# Frost5000_Sch.net
KiCad netlist of a schematic drawn in Altium Designer
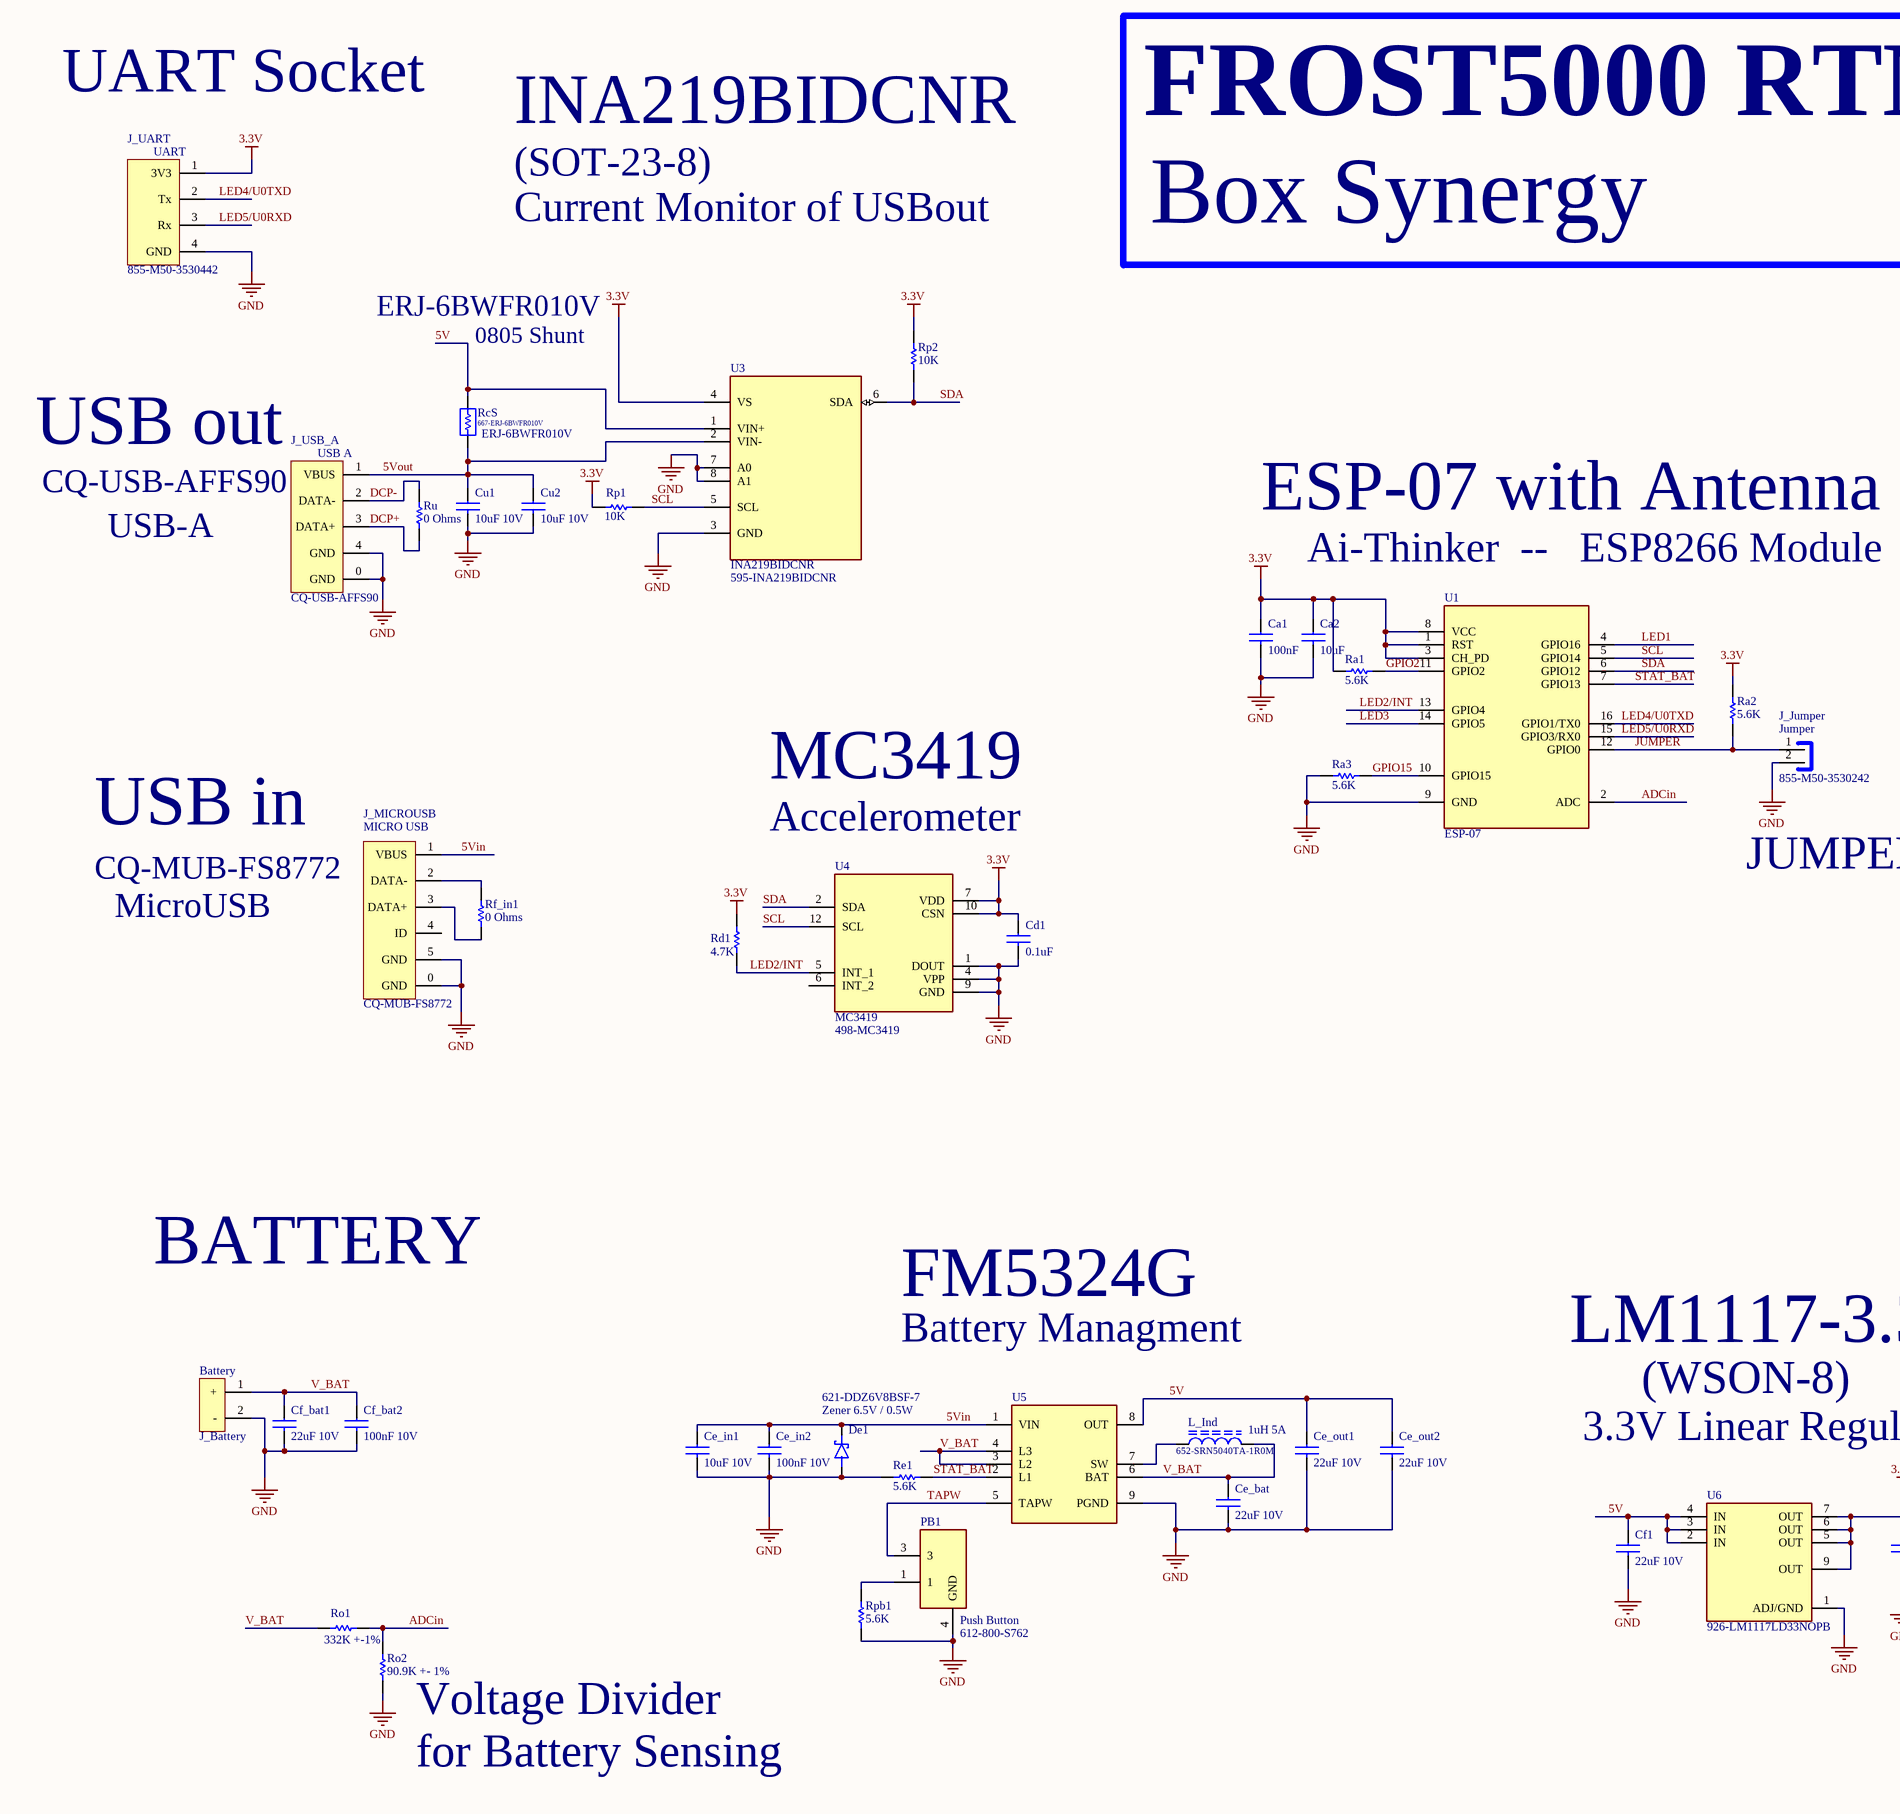
[diagram p0: Frost5000_Sch.SchDoc, left]
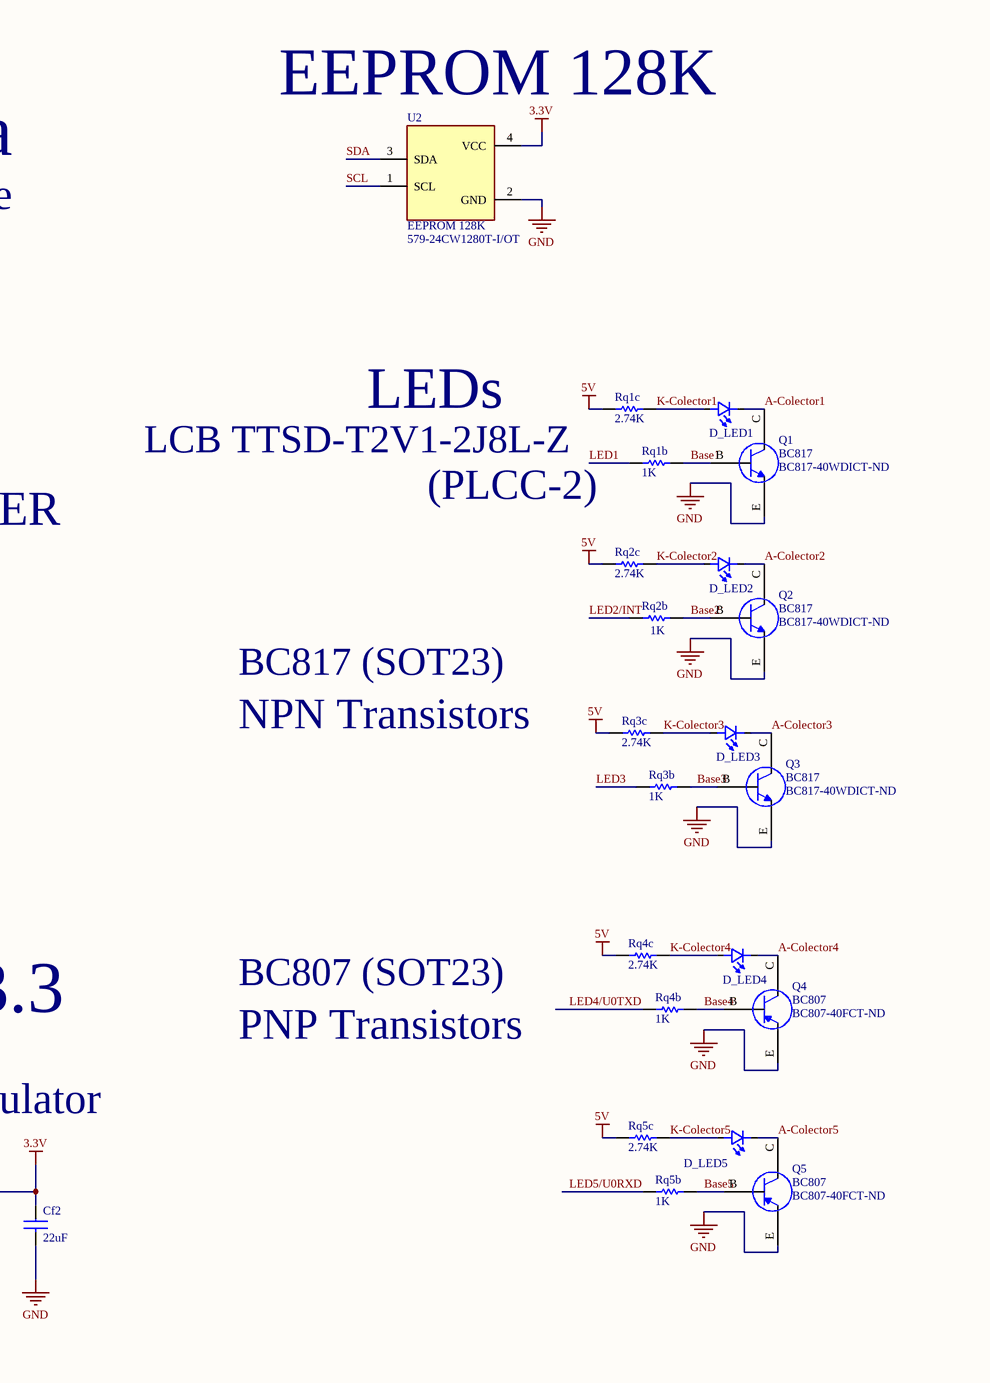
[diagram p1: Frost5000_Sch.SchDoc, right]

(export (version "E")
  (design (tool "Eeschema 10.0.6"))
  (components
    (comp (ref "Ca1")
      (value "100nF")
      (footprint "CAP_0603")
      (description "Capac Ceramic SMD 0603")
      (libsource (lib "Frost5000Beta_LIB_Pasivos_Sch") (part "Cap_0603_Ceramic"))
    )
    (comp (ref "Ca2")
      (value "10uF")
      (footprint "CAP_1206")
      (description "Capac Ceramic SMD")
      (libsource (lib "Frost5000Beta_LIB_Pasivos_Sch") (part "Cap_1206_Ceramic"))
    )
    (comp (ref "Cd1")
      (value "0.1uF")
      (footprint "CAP_0603")
      (description "Capac Ceramic SMD 0603")
      (libsource (lib "Frost5000Beta_LIB_Pasivos_Sch") (part "Cap_0603_Ceramic"))
    )
    (comp (ref "Ce_bat")
      (value "22uF 10V")
      (footprint "CAP_1206")
      (description "Capac Ceramic SMD")
      (libsource (lib "Frost5000Beta_LIB_Pasivos_Sch") (part "Cap_1206_Ceramic"))
    )
    (comp (ref "Ce_in1")
      (value "10uF 10V")
      (footprint "CAP_1206")
      (description "Capac Ceramic SMD")
      (libsource (lib "Frost5000Beta_LIB_Pasivos_Sch") (part "Cap_1206_Ceramic"))
    )
    (comp (ref "Ce_in2")
      (value "100nF 10V")
      (footprint "CAP_0603")
      (description "Capac Ceramic SMD 0603")
      (libsource (lib "Frost5000Beta_LIB_Pasivos_Sch") (part "Cap_0603_Ceramic"))
    )
    (comp (ref "Ce_out1")
      (value "22uF 10V")
      (footprint "CAP_1210")
      (description "Capac Ceramic SMD 1210")
      (libsource (lib "Frost5000Beta_LIB_Pasivos_Sch") (part "Cap_1210_Ceramic"))
    )
    (comp (ref "Ce_out2")
      (value "22uF 10V")
      (footprint "CAP_1206")
      (description "Capac Ceramic SMD")
      (libsource (lib "Frost5000Beta_LIB_Pasivos_Sch") (part "Cap_1206_Ceramic"))
    )
    (comp (ref "Cf1")
      (value "22uF 10V")
      (footprint "CAP_0603")
      (description "Capac Ceramic SMD 0603")
      (libsource (lib "Frost5000Beta_LIB_Pasivos_Sch") (part "Cap_0603_Ceramic"))
    )
    (comp (ref "Cf2")
      (value "22uF")
      (footprint "CAP_0603")
      (description "Capac Ceramic SMD 0603")
      (libsource (lib "Frost5000Beta_LIB_Pasivos_Sch") (part "Cap_0603_Ceramic"))
    )
    (comp (ref "Cf_bat1")
      (value "22uF 10V")
      (footprint "CAP_1206")
      (description "Capac Ceramic SMD")
      (libsource (lib "Frost5000Beta_LIB_Pasivos_Sch") (part "Cap_1206_Ceramic"))
    )
    (comp (ref "Cf_bat2")
      (value "100nF 10V")
      (footprint "CAP_0603")
      (description "Capac Ceramic SMD 0603")
      (libsource (lib "Frost5000Beta_LIB_Pasivos_Sch") (part "Cap_0603_Ceramic"))
    )
    (comp (ref "Cu1")
      (value "10uF 10V")
      (footprint "CAP_1206")
      (description "Capac Ceramic SMD")
      (libsource (lib "Frost5000Beta_LIB_Pasivos_Sch") (part "Cap_1206_Ceramic"))
    )
    (comp (ref "Cu2")
      (value "10uF 10V")
      (footprint "CAP_1206")
      (description "Capac Ceramic SMD")
      (libsource (lib "Frost5000Beta_LIB_Pasivos_Sch") (part "Cap_1206_Ceramic"))
    )
    (comp (ref "De1")
      (value "Zener 6.5V / 0.5W")
      (footprint "Zener-SOD323F")
      (fields
        (field (name "MF") "Littelfuse")
        (field (name "MP") "SMF5.0AT1G")
        (field (name "SUPPLIER PART NUMBER 1") "621-DDZ6V8BSF-7")
      )
      (libsource (lib "Frost5000Beta_LIB_Otros_Sch") (part "Zener"))
    )
    (comp (ref "D_LED1")
      (value "LCB TTSD-T2V1-2J8L-Z")
      (footprint "LED_PLCC-2")
      (description "Blue LED PLCC-2")
      (fields (field (name "MF") "Broadcom Limited") (field (name "MP") "HSMW-C191"))
      (libsource (lib "Frost5000Beta_LIB_Otros_Sch") (part "LCB_TTSD"))
    )
    (comp (ref "D_LED2")
      (value "LCB TTSD-T2V1-2J8L-Z")
      (footprint "LED_PLCC-2")
      (description "Blue LED PLCC-2")
      (fields (field (name "MF") "Broadcom Limited") (field (name "MP") "HSMW-C191"))
      (libsource (lib "Frost5000Beta_LIB_Otros_Sch") (part "LCB_TTSD"))
    )
    (comp (ref "D_LED3")
      (value "LCB TTSD-T2V1-2J8L-Z")
      (footprint "LED_PLCC-2")
      (description "Blue LED PLCC-2")
      (fields (field (name "MF") "Broadcom Limited") (field (name "MP") "HSMW-C191"))
      (libsource (lib "Frost5000Beta_LIB_Otros_Sch") (part "LCB_TTSD"))
    )
    (comp (ref "D_LED4")
      (value "LCB TTSD-T2V1-2J8L-Z")
      (footprint "LED_PLCC-2")
      (description "Blue LED PLCC-2")
      (fields (field (name "MF") "Broadcom Limited") (field (name "MP") "HSMW-C191"))
      (libsource (lib "Frost5000Beta_LIB_Otros_Sch") (part "LCB_TTSD"))
    )
    (comp (ref "D_LED5")
      (value "LCB TTSD-T2V1-2J8L-Z")
      (footprint "LED_PLCC-2")
      (description "Blue LED PLCC-2")
      (fields (field (name "MF") "Broadcom Limited") (field (name "MP") "HSMW-C191"))
      (libsource (lib "Frost5000Beta_LIB_Otros_Sch") (part "LCB_TTSD"))
    )
    (comp (ref "J_Battery")
      (value "Connx2_Battery")
      (footprint "Battery")
      (description "NO SOCKET")
      (libsource (lib "Frost5000Beta_LIB_Conectores_Sch") (part "Connx2_Battery"))
    )
    (comp (ref "J_Jumper")
      (value "M50-3530242")
      (footprint "JUMPER-1.27 mm")
      (description "1.27mm Pin Header 2x1")
      (fields (field (name "SUPPLIER PART NUMBER 1") "855-M50-3530242"))
      (libsource (lib "Summits7Beta_LIB_Conectores_Sch") (part "Jumper"))
    )
    (comp (ref "J_MICROUSB")
      (value "CQ-MUB-FS8772")
      (footprint "MICRO USB")
      (description "MicroUSB B-type Socket")
      (libsource (lib "Frost5000Beta_LIB_Conectores_Sch") (part "MicroUSB"))
    )
    (comp (ref "J_UART")
      (value "M50-3530442")
      (footprint "UART-1.27mm")
      (description "1.27mm Pin Header 4x1")
      (fields (field (name "SUPPLIER PART NUMBER 1") "855-M50-3530442"))
      (libsource (lib "Summits7Beta_LIB_Conectores_Sch") (part "Connx4_UART"))
    )
    (comp (ref "J_USB_A")
      (value "CQ-USB-AFFS90")
      (footprint "USB-A__IPX8")
      (description "USB-A Socket")
      (libsource (lib "Frost5000Beta_LIB_Conectores_Sch") (part "USB-A 5V"))
    )
    (comp (ref "L_Ind")
      (value "1uH 5A")
      (footprint "Inductor_SRN5040")
      (description "Inductor_SRN5040")
      (fields (field (name "MF") "Vishay Dale") (field (name "SUPPLIER PART NUMBER 1") "652-SRN5040TA-1R0M"))
      (libsource (lib "Frost5000Beta_LIB_Pasivos_Sch") (part "Ind_SRN5040"))
    )
    (comp (ref "PB1")
      (value "Push Button")
      (footprint "800C Switch")
      (description "Push Button 800C")
      (fields (field (name "SUPPLIER PART NUMBER 1") "612-800-S762"))
      (libsource (lib "Frost5000Beta_LIB_Otros_Sch") (part "800C"))
    )
    (comp (ref "Q1")
      (value "BC817")
      (footprint "Transistor_SOT23-3")
      (description "Transistor NPN")
      (fields (field (name "SUPPLIER PART NUMBER 1") "BC817-40WDICT-ND"))
      (libsource (lib "Frost5000Beta_LIB_Integrados_Sch") (part "BC817"))
    )
    (comp (ref "Q2")
      (value "BC817")
      (footprint "Transistor_SOT23-3")
      (description "Transistor NPN")
      (fields (field (name "SUPPLIER PART NUMBER 1") "BC817-40WDICT-ND"))
      (libsource (lib "Frost5000Beta_LIB_Integrados_Sch") (part "BC817"))
    )
    (comp (ref "Q3")
      (value "BC817")
      (footprint "Transistor_SOT23-3")
      (description "Transistor NPN")
      (fields (field (name "SUPPLIER PART NUMBER 1") "BC817-40WDICT-ND"))
      (libsource (lib "Frost5000Beta_LIB_Integrados_Sch") (part "BC817"))
    )
    (comp (ref "Q4")
      (value "BC807")
      (footprint "Transistor_SOT23-3")
      (description "Transistor PNP")
      (fields (field (name "SUPPLIER PART NUMBER 1") "BC807-40FCT-ND"))
      (libsource (lib "Frost5000Beta_LIB_Integrados_Sch") (part "BC807"))
    )
    (comp (ref "Q5")
      (value "BC807")
      (footprint "Transistor_SOT23-3")
      (description "Transistor PNP")
      (fields (field (name "SUPPLIER PART NUMBER 1") "BC807-40FCT-ND"))
      (libsource (lib "Frost5000Beta_LIB_Integrados_Sch") (part "BC807"))
    )
    (comp (ref "Ra1")
      (value "5.6K")
      (footprint "RES_0603")
      (description "Resistor SMD")
      (fields (field (name "PUBLISHER") "Altium Limited"))
      (libsource (lib "Frost5000Beta_LIB_Pasivos_Sch") (part "Res_0603"))
    )
    (comp (ref "Ra2")
      (value "5.6K")
      (footprint "RES_0603")
      (description "Resistor SMD")
      (fields (field (name "PUBLISHER") "Altium Limited"))
      (libsource (lib "Frost5000Beta_LIB_Pasivos_Sch") (part "Res_0603"))
    )
    (comp (ref "Ra3")
      (value "5.6K")
      (footprint "RES_0603")
      (description "Resistor SMD")
      (fields (field (name "PUBLISHER") "Altium Limited"))
      (libsource (lib "Frost5000Beta_LIB_Pasivos_Sch") (part "Res_0603"))
    )
    (comp (ref "RcS")
      (value "ERJ-6BWFR010V")
      (footprint "RES-SHUNT-0805")
      (description "Shunt 0.01 Ohm 0.5W 1% SMD Resistor")
      (fields
        (field (name "SUPPLIER PART NUMBER 1") "667-ERJ-6BWFR010V")
        (field (name "PUBLISHER") "Altium Limited")
      )
      (libsource (lib "Frost5000Beta_LIB_Pasivos_Sch") (part "Shunt_0805"))
    )
    (comp (ref "Rd1")
      (value "4.7K")
      (footprint "RES_0603")
      (description "Resistor SMD")
      (fields (field (name "PUBLISHER") "Altium Limited"))
      (libsource (lib "Frost5000Beta_LIB_Pasivos_Sch") (part "Res_0603"))
    )
    (comp (ref "Re1")
      (value "5.6K")
      (footprint "RES_0603")
      (description "Resistor SMD")
      (fields (field (name "PUBLISHER") "Altium Limited"))
      (libsource (lib "Frost5000Beta_LIB_Pasivos_Sch") (part "Res_0603"))
    )
    (comp (ref "Rf_in1")
      (value "0 Ohms")
      (footprint "RES_0603")
      (description "Resistor SMD")
      (fields (field (name "PUBLISHER") "Altium Limited"))
      (libsource (lib "Frost5000Beta_LIB_Pasivos_Sch") (part "Res_0603"))
    )
    (comp (ref "Ro1")
      (value "332K +-1%")
      (footprint "RES_0603")
      (description "Resistor SMD")
      (fields (field (name "PUBLISHER") "Altium Limited"))
      (libsource (lib "Frost5000Beta_LIB_Pasivos_Sch") (part "Res_0603"))
    )
    (comp (ref "Ro2")
      (value "90.9K +- 1%")
      (footprint "RES_0603")
      (description "Resistor SMD")
      (fields (field (name "PUBLISHER") "Altium Limited"))
      (libsource (lib "Frost5000Beta_LIB_Pasivos_Sch") (part "Res_0603"))
    )
    (comp (ref "Rp1")
      (value "10K")
      (footprint "RES_0603")
      (description "Resistor SMD")
      (fields (field (name "PUBLISHER") "Altium Limited"))
      (libsource (lib "Frost5000Beta_LIB_Pasivos_Sch") (part "Res_0603"))
    )
    (comp (ref "Rp2")
      (value "10K")
      (footprint "RES_0603")
      (description "Resistor SMD")
      (fields (field (name "PUBLISHER") "Altium Limited"))
      (libsource (lib "Frost5000Beta_LIB_Pasivos_Sch") (part "Res_0603"))
    )
    (comp (ref "Rpb1")
      (value "5.6K")
      (footprint "RES_0603")
      (description "Resistor SMD")
      (fields (field (name "PUBLISHER") "Altium Limited"))
      (libsource (lib "Frost5000Beta_LIB_Pasivos_Sch") (part "Res_0603"))
    )
    (comp (ref "Rq1b")
      (value "1K")
      (footprint "RES_0603")
      (description "Resistor SMD")
      (fields (field (name "PUBLISHER") "Altium Limited"))
      (libsource (lib "Frost5000Beta_LIB_Pasivos_Sch") (part "Res_0603"))
    )
    (comp (ref "Rq1c")
      (value "2.74K")
      (footprint "RES_0603")
      (description "Resistor SMD")
      (fields (field (name "PUBLISHER") "Altium Limited"))
      (libsource (lib "Frost5000Beta_LIB_Pasivos_Sch") (part "Res_0603"))
    )
    (comp (ref "Rq2b")
      (value "1K")
      (footprint "RES_0603")
      (description "Resistor SMD")
      (fields (field (name "PUBLISHER") "Altium Limited"))
      (libsource (lib "Frost5000Beta_LIB_Pasivos_Sch") (part "Res_0603"))
    )
    (comp (ref "Rq2c")
      (value "2.74K")
      (footprint "RES_0603")
      (description "Resistor SMD")
      (fields (field (name "PUBLISHER") "Altium Limited"))
      (libsource (lib "Frost5000Beta_LIB_Pasivos_Sch") (part "Res_0603"))
    )
    (comp (ref "Rq3b")
      (value "1K")
      (footprint "RES_0603")
      (description "Resistor SMD")
      (fields (field (name "PUBLISHER") "Altium Limited"))
      (libsource (lib "Frost5000Beta_LIB_Pasivos_Sch") (part "Res_0603"))
    )
    (comp (ref "Rq3c")
      (value "2.74K")
      (footprint "RES_0603")
      (description "Resistor SMD")
      (fields (field (name "PUBLISHER") "Altium Limited"))
      (libsource (lib "Frost5000Beta_LIB_Pasivos_Sch") (part "Res_0603"))
    )
    (comp (ref "Rq4b")
      (value "1K")
      (footprint "RES_0603")
      (description "Resistor SMD")
      (fields (field (name "PUBLISHER") "Altium Limited"))
      (libsource (lib "Frost5000Beta_LIB_Pasivos_Sch") (part "Res_0603"))
    )
    (comp (ref "Rq4c")
      (value "2.74K")
      (footprint "RES_0603")
      (description "Resistor SMD")
      (fields (field (name "PUBLISHER") "Altium Limited"))
      (libsource (lib "Frost5000Beta_LIB_Pasivos_Sch") (part "Res_0603"))
    )
    (comp (ref "Rq5b")
      (value "1K")
      (footprint "RES_0603")
      (description "Resistor SMD")
      (fields (field (name "PUBLISHER") "Altium Limited"))
      (libsource (lib "Frost5000Beta_LIB_Pasivos_Sch") (part "Res_0603"))
    )
    (comp (ref "Rq5c")
      (value "2.74K")
      (footprint "RES_0603")
      (description "Resistor SMD")
      (fields (field (name "PUBLISHER") "Altium Limited"))
      (libsource (lib "Frost5000Beta_LIB_Pasivos_Sch") (part "Res_0603"))
    )
    (comp (ref "Ru")
      (value "0 Ohms")
      (footprint "RES_0603")
      (description "Resistor SMD")
      (fields (field (name "PUBLISHER") "Altium Limited"))
      (libsource (lib "Frost5000Beta_LIB_Pasivos_Sch") (part "Res_0603"))
    )
    (comp (ref "U1")
      (value "ESP-07")
      (footprint "ESP-07")
      (description "ESP07 Module with Antenna Ai-Thinker")
      (fields (field (name "MP") "AP65111AWU-7") (field (name "MF") "Diodes Inc."))
      (libsource (lib "Frost5000Beta_LIB_Integrados_Sch") (part "ESP-07"))
    )
    (comp (ref "U2")
      (value "EEPROM 128K")
      (footprint "24CW128")
      (fields (field (name "SUPPLIER PART NUMBER 1") "579-24CW1280T-I/OT"))
      (libsource (lib "Frost5000Beta_LIB_Integrados_Sch") (part "24CW1280T-I/OT"))
    )
    (comp (ref "U3")
      (value "INA219BIDCNR")
      (footprint "INA219B SOT23")
      (description "Current Monitor Regulator High-Side 10mA SOT-23-8")
      (fields
        (field (name "DIGI-KEY_PART_NUMBER") "296-46420-1-ND")
        (field (name "MF") "Texas Instruments")
        (field (name "SUPPLIER PART NUMBER 1") "595-INA219BIDCNR")
      )
      (libsource (lib "Frost5000Beta_LIB_Integrados_Sch") (part "INA219BIDCNR"))
    )
    (comp (ref "U4")
      (value "MC3419")
      (footprint "MC3419")
      (description "Accelerometer")
      (fields
        (field (name "MP") "LSM303AGR")
        (field (name "MF") "STMicroelectronics")
        (field (name "SUPPLIER PART NUMBER 1") "498-MC3419")
      )
      (libsource (lib "Frost5000Beta_LIB_Integrados_Sch") (part "MC3419"))
    )
    (comp (ref "U5")
      (value "FM5324G")
      (footprint "SOP8")
      (description "Power Battery Management IC")
      (fields (field (name "MP") "LT1117IST-5#PBF") (field (name "MF") "Analog Devices"))
      (libsource (lib "Frost5000Beta_LIB_Integrados_Sch") (part "FM5324G"))
    )
    (comp (ref "U6")
      (value "LM1117LD-3.3/NOPB")
      (footprint "LM1117-3.3-WSON-8")
      (description "LDO Regulator Pos 3.3V 0.8A Texas - WSON8")
      (fields
        (field (name "MP") "LT1117IST-5#PBF")
        (field (name "MF") "Analog Devices")
        (field (name "SUPPLIER PART NUMBER 1") "926-LM1117LD33NOPB")
      )
      (libsource (lib "Frost5000Beta_LIB_Integrados_Sch") (part "LM1117LD-3.3/NOPB"))
    )
  )
  (nets
    (net (code "1") (name "/5Vin") (class "Default")
      (node (ref "Ce_in1") (pin "1") (pinfunction "1_1") (pintype "passive"))
      (node (ref "Ce_in2") (pin "1") (pinfunction "1_1") (pintype "passive"))
      (node (ref "De1") (pin "C") (pinfunction "C_C") (pintype "passive"))
      (node (ref "J_MICROUSB") (pin "1") (pinfunction "VBUS_1") (pintype "power_in"))
      (node (ref "U5") (pin "1") (pinfunction "VIN_1") (pintype "passive"))
    )
    (net (code "2") (name "/5Vout") (class "Default")
      (node (ref "Cu1") (pin "1") (pinfunction "1_1") (pintype "passive"))
      (node (ref "Cu2") (pin "1") (pinfunction "1_1") (pintype "passive"))
      (node (ref "J_USB_A") (pin "1") (pinfunction "VBUS_1") (pintype "power_in"))
      (node (ref "RcS") (pin "1") (pinfunction "1_1") (pintype "passive"))
      (node (ref "U3") (pin "2") (pinfunction "VIN-_2") (pintype "passive"))
    )
    (net (code "3") (name "/A-Colector1") (class "Default")
      (node (ref "D_LED1") (pin "1") (pinfunction "K_1") (pintype "passive"))
      (node (ref "Q1") (pin "C") (pinfunction "C_C") (pintype "passive"))
    )
    (net (code "4") (name "/A-Colector2") (class "Default")
      (node (ref "D_LED2") (pin "1") (pinfunction "K_1") (pintype "passive"))
      (node (ref "Q2") (pin "C") (pinfunction "C_C") (pintype "passive"))
    )
    (net (code "5") (name "/A-Colector3") (class "Default")
      (node (ref "D_LED3") (pin "1") (pinfunction "K_1") (pintype "passive"))
      (node (ref "Q3") (pin "C") (pinfunction "C_C") (pintype "passive"))
    )
    (net (code "6") (name "/A-Colector4") (class "Default")
      (node (ref "D_LED4") (pin "1") (pinfunction "K_1") (pintype "passive"))
      (node (ref "Q4") (pin "C") (pinfunction "C_C") (pintype "passive"))
    )
    (net (code "7") (name "/A-Colector5") (class "Default")
      (node (ref "D_LED5") (pin "1") (pinfunction "K_1") (pintype "passive"))
      (node (ref "Q5") (pin "C") (pinfunction "C_C") (pintype "passive"))
    )
    (net (code "8") (name "/ADCin") (class "Default")
      (node (ref "Ro1") (pin "2") (pinfunction "2_2") (pintype "passive"))
      (node (ref "Ro2") (pin "2") (pinfunction "2_2") (pintype "passive"))
      (node (ref "U1") (pin "2") (pinfunction "ADC_2") (pintype "passive"))
    )
    (net (code "9") (name "/Base1") (class "Default")
      (node (ref "Q1") (pin "B") (pinfunction "B_B") (pintype "passive"))
      (node (ref "Rq1b") (pin "1") (pinfunction "1_1") (pintype "passive"))
    )
    (net (code "10") (name "/Base2") (class "Default")
      (node (ref "Q2") (pin "B") (pinfunction "B_B") (pintype "passive"))
      (node (ref "Rq2b") (pin "1") (pinfunction "1_1") (pintype "passive"))
    )
    (net (code "11") (name "/Base3") (class "Default")
      (node (ref "Q3") (pin "B") (pinfunction "B_B") (pintype "passive"))
      (node (ref "Rq3b") (pin "1") (pinfunction "1_1") (pintype "passive"))
    )
    (net (code "12") (name "/Base4") (class "Default")
      (node (ref "Q4") (pin "B") (pinfunction "B_B") (pintype "passive"))
      (node (ref "Rq4b") (pin "1") (pinfunction "1_1") (pintype "passive"))
    )
    (net (code "13") (name "/Base5") (class "Default")
      (node (ref "Q5") (pin "B") (pinfunction "B_B") (pintype "passive"))
      (node (ref "Rq5b") (pin "1") (pinfunction "1_1") (pintype "passive"))
    )
    (net (code "14") (name "/DCP+") (class "Default")
      (node (ref "J_USB_A") (pin "3") (pinfunction "DATA+_3") (pintype "passive"))
      (node (ref "Ru") (pin "1") (pinfunction "1_1") (pintype "passive"))
    )
    (net (code "15") (name "/DCP-") (class "Default")
      (node (ref "J_USB_A") (pin "2") (pinfunction "DATA-_2") (pintype "passive"))
      (node (ref "Ru") (pin "2") (pinfunction "2_2") (pintype "passive"))
    )
    (net (code "16") (name "/GPIO2") (class "Default")
      (node (ref "Ra1") (pin "1") (pinfunction "1_1") (pintype "passive"))
      (node (ref "U1") (pin "11") (pinfunction "GPIO2_11") (pintype "passive"))
    )
    (net (code "17") (name "/GPIO15") (class "Default")
      (node (ref "Ra3") (pin "1") (pinfunction "1_1") (pintype "passive"))
      (node (ref "U1") (pin "10") (pinfunction "GPIO15_10") (pintype "passive"))
    )
    (net (code "18") (name "/JUMPER") (class "Default")
      (node (ref "J_Jumper") (pin "1") (pinfunction "1_1") (pintype "passive"))
      (node (ref "Ra2") (pin "1") (pinfunction "1_1") (pintype "passive"))
      (node (ref "U1") (pin "12") (pinfunction "GPIO0_12") (pintype "passive"))
    )
    (net (code "19") (name "/K-Colector1") (class "Default")
      (node (ref "D_LED1") (pin "2") (pinfunction "A_2") (pintype "passive"))
      (node (ref "Rq1c") (pin "1") (pinfunction "1_1") (pintype "passive"))
    )
    (net (code "20") (name "/K-Colector2") (class "Default")
      (node (ref "D_LED2") (pin "2") (pinfunction "A_2") (pintype "passive"))
      (node (ref "Rq2c") (pin "1") (pinfunction "1_1") (pintype "passive"))
    )
    (net (code "21") (name "/K-Colector3") (class "Default")
      (node (ref "D_LED3") (pin "2") (pinfunction "A_2") (pintype "passive"))
      (node (ref "Rq3c") (pin "1") (pinfunction "1_1") (pintype "passive"))
    )
    (net (code "22") (name "/K-Colector4") (class "Default")
      (node (ref "D_LED4") (pin "2") (pinfunction "A_2") (pintype "passive"))
      (node (ref "Rq4c") (pin "1") (pinfunction "1_1") (pintype "passive"))
    )
    (net (code "23") (name "/K-Colector5") (class "Default")
      (node (ref "D_LED5") (pin "2") (pinfunction "A_2") (pintype "passive"))
      (node (ref "Rq5c") (pin "1") (pinfunction "1_1") (pintype "passive"))
    )
    (net (code "24") (name "/LED1") (class "Default")
      (node (ref "Rq1b") (pin "2") (pinfunction "2_2") (pintype "passive"))
      (node (ref "U1") (pin "4") (pinfunction "GPIO16_4") (pintype "passive"))
    )
    (net (code "25") (name "/LED2{slash}INT") (class "Default")
      (node (ref "Rd1") (pin "2") (pinfunction "2_2") (pintype "passive"))
      (node (ref "Rq2b") (pin "2") (pinfunction "2_2") (pintype "passive"))
      (node (ref "U1") (pin "13") (pinfunction "GPIO4_13") (pintype "passive"))
      (node (ref "U4") (pin "5") (pinfunction "INT_1_5") (pintype "passive"))
    )
    (net (code "26") (name "/LED3") (class "Default")
      (node (ref "Rq3b") (pin "2") (pinfunction "2_2") (pintype "passive"))
      (node (ref "U1") (pin "14") (pinfunction "GPIO5_14") (pintype "passive"))
    )
    (net (code "27") (name "/LED4{slash}U0TXD") (class "Default")
      (node (ref "J_UART") (pin "2") (pinfunction "Tx_2") (pintype "passive"))
      (node (ref "Rq4b") (pin "2") (pinfunction "2_2") (pintype "passive"))
      (node (ref "U1") (pin "16") (pinfunction "GPIO1/TX0_16") (pintype "passive"))
    )
    (net (code "28") (name "/LED5{slash}U0RXD") (class "Default")
      (node (ref "J_UART") (pin "3") (pinfunction "Rx_3") (pintype "passive"))
      (node (ref "Rq5b") (pin "2") (pinfunction "2_2") (pintype "passive"))
      (node (ref "U1") (pin "15") (pinfunction "GPIO3/RX0_15") (pintype "passive"))
    )
    (net (code "29") (name "/SCL") (class "Default")
      (node (ref "Rp1") (pin "2") (pinfunction "2_2") (pintype "passive"))
      (node (ref "U1") (pin "5") (pinfunction "GPIO14_5") (pintype "passive"))
      (node (ref "U2") (pin "1") (pinfunction "SCL_1") (pintype "passive"))
      (node (ref "U3") (pin "5") (pinfunction "SCL_5") (pintype "passive"))
      (node (ref "U4") (pin "12") (pinfunction "SCL_12") (pintype "passive"))
    )
    (net (code "30") (name "/SDA") (class "Default")
      (node (ref "Rp2") (pin "2") (pinfunction "2_2") (pintype "passive"))
      (node (ref "U1") (pin "6") (pinfunction "GPIO12_6") (pintype "passive"))
      (node (ref "U2") (pin "3") (pinfunction "SDA_3") (pintype "passive"))
      (node (ref "U3") (pin "6") (pinfunction "SDA_6") (pintype "bidirectional"))
      (node (ref "U4") (pin "2") (pinfunction "SDA_2") (pintype "passive"))
    )
    (net (code "31") (name "/STAT_BAT") (class "Default")
      (node (ref "Re1") (pin "1") (pinfunction "1_1") (pintype "passive"))
      (node (ref "U1") (pin "7") (pinfunction "GPIO13_7") (pintype "passive"))
      (node (ref "U5") (pin "2") (pinfunction "L1_2") (pintype "passive"))
    )
    (net (code "32") (name "/TAPW") (class "Default")
      (node (ref "PB1") (pin "3") (pinfunction "3_3") (pintype "passive"))
      (node (ref "U5") (pin "5") (pinfunction "TAPW_5") (pintype "passive"))
    )
    (net (code "33") (name "/V_BAT") (class "Default")
      (node (ref "Ce_bat") (pin "1") (pinfunction "1_1") (pintype "passive"))
      (node (ref "Cf_bat1") (pin "1") (pinfunction "1_1") (pintype "passive"))
      (node (ref "Cf_bat2") (pin "1") (pinfunction "1_1") (pintype "passive"))
      (node (ref "J_Battery") (pin "1") (pinfunction "+_1") (pintype "passive"))
      (node (ref "L_Ind") (pin "1") (pinfunction "1_1") (pintype "passive"))
      (node (ref "Ro1") (pin "1") (pinfunction "1_1") (pintype "passive"))
      (node (ref "U5") (pin "3") (pinfunction "L2_3") (pintype "passive"))
      (node (ref "U5") (pin "4") (pinfunction "L3_4") (pintype "passive"))
      (node (ref "U5") (pin "6") (pinfunction "BAT_6") (pintype "passive"))
    )
    (net (code "34") (name "3.3V") (class "Default")
      (node (ref "Ca1") (pin "1") (pinfunction "1_1") (pintype "passive"))
      (node (ref "Ca2") (pin "1") (pinfunction "1_1") (pintype "passive"))
      (node (ref "Cd1") (pin "1") (pinfunction "1_1") (pintype "passive"))
      (node (ref "Cf2") (pin "1") (pinfunction "1_1") (pintype "passive"))
      (node (ref "J_UART") (pin "1") (pinfunction "3V3_1") (pintype "passive"))
      (node (ref "Ra1") (pin "2") (pinfunction "2_2") (pintype "passive"))
      (node (ref "Ra2") (pin "2") (pinfunction "2_2") (pintype "passive"))
      (node (ref "Rd1") (pin "1") (pinfunction "1_1") (pintype "passive"))
      (node (ref "Rp1") (pin "1") (pinfunction "1_1") (pintype "passive"))
      (node (ref "Rp2") (pin "1") (pinfunction "1_1") (pintype "passive"))
      (node (ref "U1") (pin "1") (pinfunction "RST_1") (pintype "passive"))
      (node (ref "U1") (pin "3") (pinfunction "CH_PD_3") (pintype "passive"))
      (node (ref "U1") (pin "8") (pinfunction "VCC_8") (pintype "passive"))
      (node (ref "U2") (pin "4") (pinfunction "VCC_4") (pintype "passive"))
      (node (ref "U3") (pin "4") (pinfunction "VS_4") (pintype "power_in"))
      (node (ref "U4") (pin "10") (pinfunction "CSN_10") (pintype "passive"))
      (node (ref "U4") (pin "7") (pinfunction "VDD_7") (pintype "passive"))
      (node (ref "U6") (pin "5") (pinfunction "OUT_5") (pintype "passive"))
      (node (ref "U6") (pin "6") (pinfunction "OUT_6") (pintype "passive"))
      (node (ref "U6") (pin "7") (pinfunction "OUT_7") (pintype "passive"))
      (node (ref "U6") (pin "9") (pinfunction "OUT_9") (pintype "passive"))
    )
    (net (code "35") (name "5V") (class "Default")
      (node (ref "Ce_out1") (pin "1") (pinfunction "1_1") (pintype "passive"))
      (node (ref "Ce_out2") (pin "1") (pinfunction "1_1") (pintype "passive"))
      (node (ref "Cf1") (pin "1") (pinfunction "1_1") (pintype "passive"))
      (node (ref "RcS") (pin "2") (pinfunction "2_2") (pintype "passive"))
      (node (ref "Rq1c") (pin "2") (pinfunction "2_2") (pintype "passive"))
      (node (ref "Rq2c") (pin "2") (pinfunction "2_2") (pintype "passive"))
      (node (ref "Rq3c") (pin "2") (pinfunction "2_2") (pintype "passive"))
      (node (ref "Rq4c") (pin "2") (pinfunction "2_2") (pintype "passive"))
      (node (ref "Rq5c") (pin "2") (pinfunction "2_2") (pintype "passive"))
      (node (ref "U3") (pin "1") (pinfunction "VIN+_1") (pintype "passive"))
      (node (ref "U5") (pin "8") (pinfunction "OUT_8") (pintype "passive"))
      (node (ref "U6") (pin "2") (pinfunction "IN_2") (pintype "passive"))
      (node (ref "U6") (pin "3") (pinfunction "IN_3") (pintype "passive"))
      (node (ref "U6") (pin "4") (pinfunction "IN_4") (pintype "passive"))
    )
    (net (code "36") (name "GND") (class "Default")
      (node (ref "Ca1") (pin "2") (pinfunction "2_2") (pintype "passive"))
      (node (ref "Ca2") (pin "2") (pinfunction "2_2") (pintype "passive"))
      (node (ref "Cd1") (pin "2") (pinfunction "2_2") (pintype "passive"))
      (node (ref "Ce_bat") (pin "2") (pinfunction "2_2") (pintype "passive"))
      (node (ref "Ce_in1") (pin "2") (pinfunction "2_2") (pintype "passive"))
      (node (ref "Ce_in2") (pin "2") (pinfunction "2_2") (pintype "passive"))
      (node (ref "Ce_out1") (pin "2") (pinfunction "2_2") (pintype "passive"))
      (node (ref "Ce_out2") (pin "2") (pinfunction "2_2") (pintype "passive"))
      (node (ref "Cf1") (pin "2") (pinfunction "2_2") (pintype "passive"))
      (node (ref "Cf2") (pin "2") (pinfunction "2_2") (pintype "passive"))
      (node (ref "Cf_bat1") (pin "2") (pinfunction "2_2") (pintype "passive"))
      (node (ref "Cf_bat2") (pin "2") (pinfunction "2_2") (pintype "passive"))
      (node (ref "Cu1") (pin "2") (pinfunction "2_2") (pintype "passive"))
      (node (ref "Cu2") (pin "2") (pinfunction "2_2") (pintype "passive"))
      (node (ref "De1") (pin "A") (pinfunction "A_A") (pintype "passive"))
      (node (ref "J_Battery") (pin "2") (pinfunction "-_2") (pintype "passive"))
      (node (ref "J_Jumper") (pin "2") (pinfunction "2_2") (pintype "passive"))
      (node (ref "J_MICROUSB") (pin "0") (pinfunction "GND_0") (pintype "passive"))
      (node (ref "J_MICROUSB") (pin "5") (pinfunction "GND_5") (pintype "passive"))
      (node (ref "J_UART") (pin "4") (pinfunction "GND_4") (pintype "passive"))
      (node (ref "J_USB_A") (pin "0") (pinfunction "GND_0") (pintype "passive"))
      (node (ref "J_USB_A") (pin "4") (pinfunction "GND_4") (pintype "passive"))
      (node (ref "PB1") (pin "4") (pinfunction "GND_4") (pintype "passive"))
      (node (ref "Q1") (pin "E") (pinfunction "E_E") (pintype "passive"))
      (node (ref "Q2") (pin "E") (pinfunction "E_E") (pintype "passive"))
      (node (ref "Q3") (pin "E") (pinfunction "E_E") (pintype "passive"))
      (node (ref "Q4") (pin "E") (pinfunction "E_E") (pintype "passive"))
      (node (ref "Q5") (pin "E") (pinfunction "E_E") (pintype "passive"))
      (node (ref "Ra3") (pin "2") (pinfunction "2_2") (pintype "passive"))
      (node (ref "Re1") (pin "2") (pinfunction "2_2") (pintype "passive"))
      (node (ref "Ro2") (pin "1") (pinfunction "1_1") (pintype "passive"))
      (node (ref "Rpb1") (pin "2") (pinfunction "2_2") (pintype "passive"))
      (node (ref "U1") (pin "9") (pinfunction "GND_9") (pintype "passive"))
      (node (ref "U2") (pin "2") (pinfunction "GND_2") (pintype "passive"))
      (node (ref "U3") (pin "3") (pinfunction "GND_3") (pintype "passive"))
      (node (ref "U3") (pin "7") (pinfunction "A0_7") (pintype "passive"))
      (node (ref "U3") (pin "8") (pinfunction "A1_8") (pintype "passive"))
      (node (ref "U4") (pin "1") (pinfunction "DOUT_1") (pintype "passive"))
      (node (ref "U4") (pin "4") (pinfunction "VPP_4") (pintype "passive"))
      (node (ref "U4") (pin "9") (pinfunction "GND_9") (pintype "passive"))
      (node (ref "U5") (pin "9") (pinfunction "PGND_9") (pintype "passive"))
      (node (ref "U6") (pin "1") (pinfunction "ADJ/GND_1") (pintype "passive"))
    )
    (net (code "37") (name "Net-(J_MICROUSB-DATA+)") (class "Default")
      (node (ref "J_MICROUSB") (pin "3") (pinfunction "DATA+_3") (pintype "passive"))
      (node (ref "Rf_in1") (pin "2") (pinfunction "2_2") (pintype "passive"))
    )
    (net (code "38") (name "Net-(J_MICROUSB-DATA-)") (class "Default")
      (node (ref "J_MICROUSB") (pin "2") (pinfunction "DATA-_2") (pintype "passive"))
      (node (ref "Rf_in1") (pin "1") (pinfunction "1_1") (pintype "passive"))
    )
    (net (code "39") (name "Net-(PB1-Pad1)") (class "Default")
      (node (ref "PB1") (pin "1") (pinfunction "1_1") (pintype "passive"))
      (node (ref "Rpb1") (pin "1") (pinfunction "1_1") (pintype "passive"))
    )
    (net (code "40") (name "Net-(U5-SW)") (class "Default")
      (node (ref "L_Ind") (pin "2") (pinfunction "2_2") (pintype "passive"))
      (node (ref "U5") (pin "7") (pinfunction "SW_7") (pintype "passive"))
    )
    (net (code "41") (name "unconnected-(J_MICROUSB-ID-Pad4)") (class "Default")
      (node (ref "J_MICROUSB") (pin "4") (pinfunction "ID_4") (pintype "passive"))
    )
    (net (code "42") (name "unconnected-(U4-INT_2-Pad6)") (class "Default")
      (node (ref "U4") (pin "6") (pinfunction "INT_2_6") (pintype "passive"))
    )
  )
)
